# analogmic.net
KiCad netlist of a schematic drawn in EAGLE
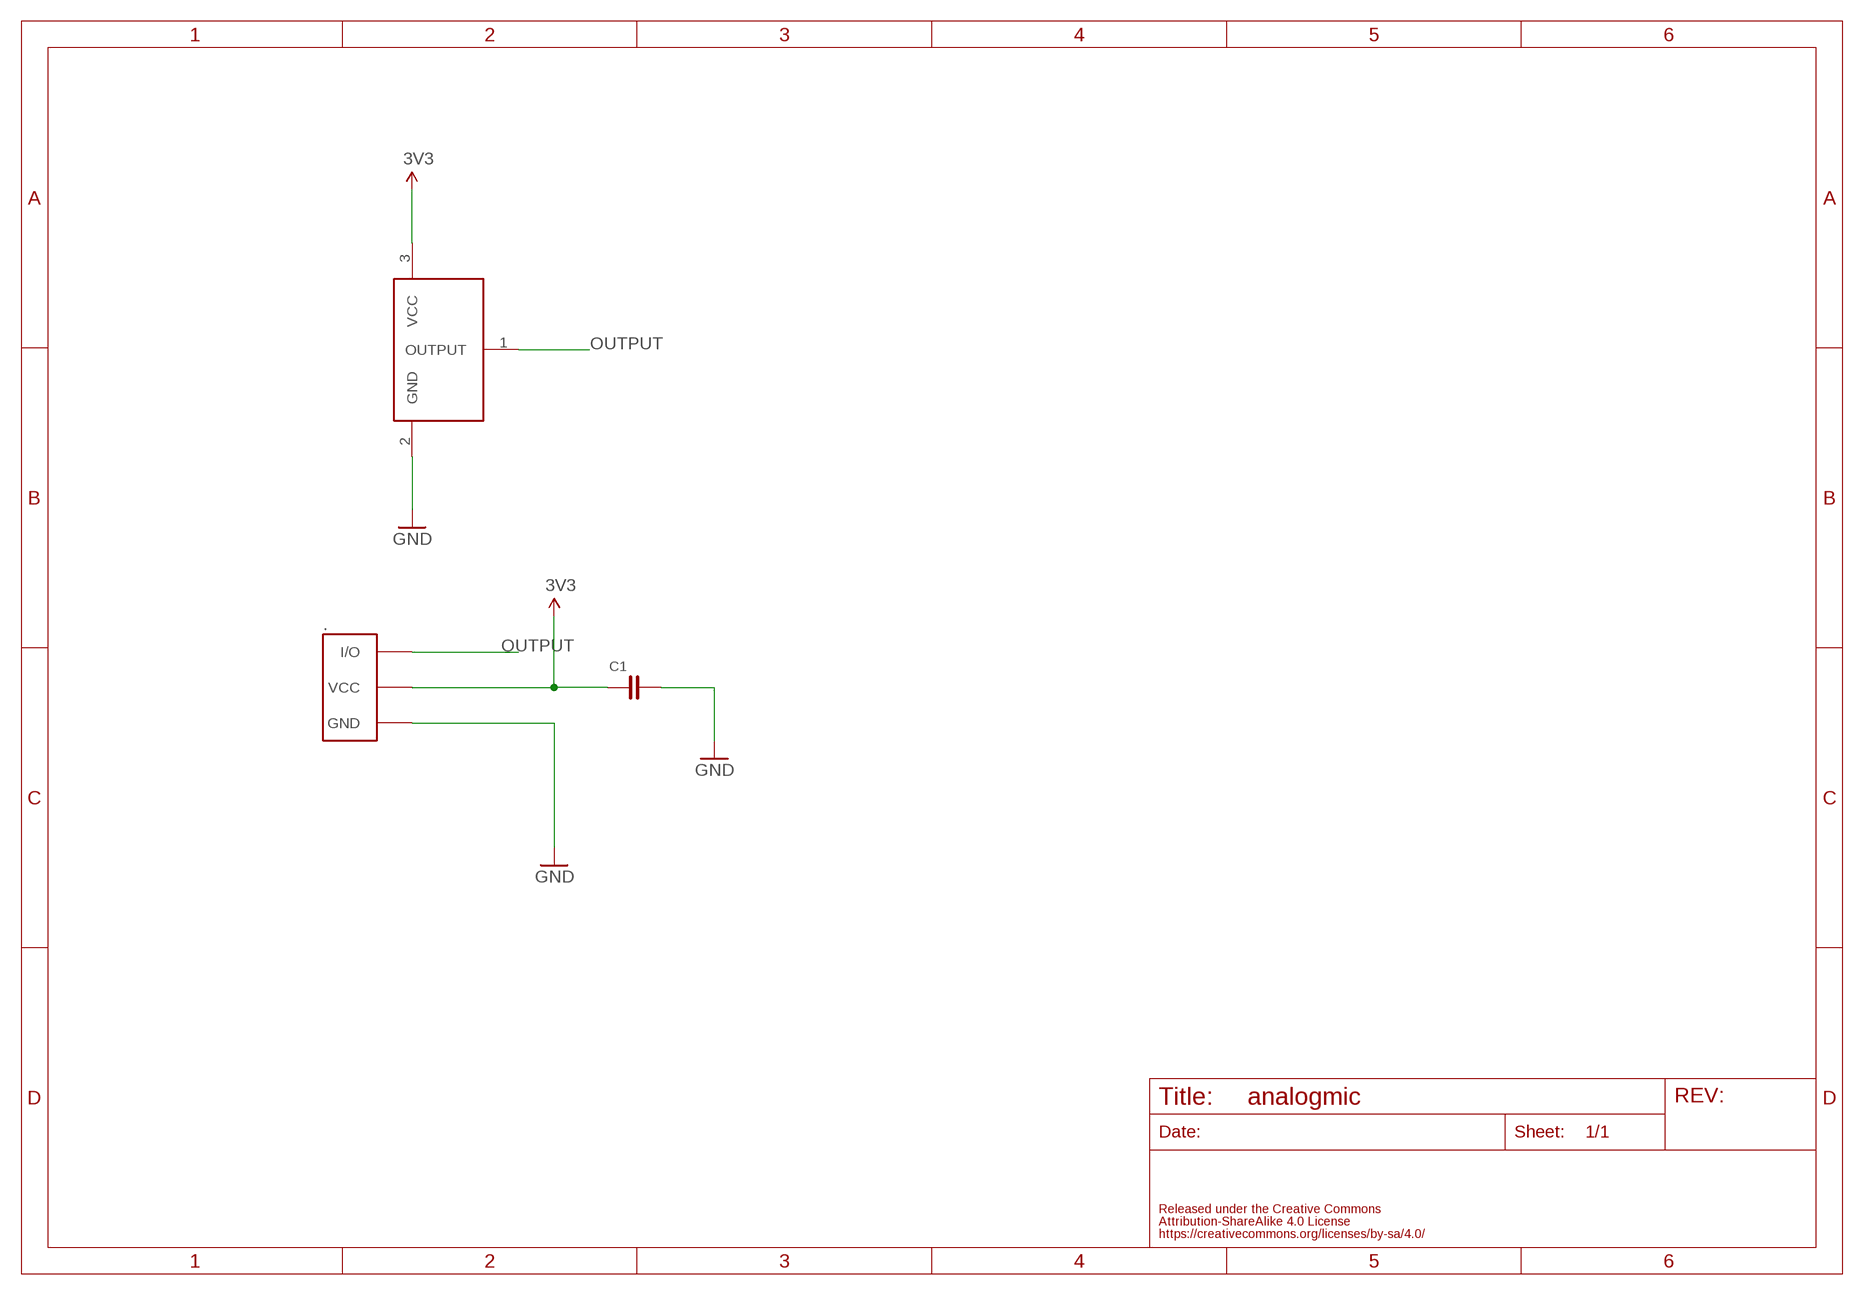
[diagram p0: schematic, sheet 1]

(export (version "E")
  (design (tool "Eeschema 10.0.6"))
  (components
    (comp (ref ".")
      (value "FABO_BRICK_3PIN-S03B-PASK-2")
      (footprint "eagle-import:FABO_BRICK_3PIN_S03B-PASK-2")
      (libsource (lib "eagle-import") (part "FABO_BRICK_3PIN-S03B-PASK-2"))
    )
    (comp (ref "C1")
      (value "CAPACITOR-0603")
      (footprint "eagle-import:0603")
      (libsource (lib "eagle-import") (part "CAPACITOR-0603"))
    )
    (comp (ref "ICS-40310")
      (value "ANALOG-MIC")
      (footprint "eagle-import:ICS40310")
      (libsource (lib "eagle-import") (part "ANALOG-MIC"))
    )
  )
  (nets
    (net (code "1") (name "/OUTPUT") (class "Default")
      (node (ref ".") (pin "I/O") (pinfunction "I/O_I/O") (pintype "bidirectional"))
      (node (ref "ICS-40310") (pin "1") (pinfunction "OUTPUT_1") (pintype "bidirectional"))
    )
    (net (code "2") (name "3V3") (class "Default")
      (node (ref ".") (pin "VCC") (pinfunction "VCC_VCC") (pintype "bidirectional"))
      (node (ref "C1") (pin "1") (pinfunction "1_1") (pintype "passive"))
      (node (ref "ICS-40310") (pin "3") (pinfunction "VCC_3") (pintype "bidirectional"))
    )
    (net (code "3") (name "GND") (class "Default")
      (node (ref ".") (pin "GND") (pinfunction "GND_GND") (pintype "bidirectional"))
      (node (ref "C1") (pin "2") (pinfunction "2_2") (pintype "passive"))
      (node (ref "ICS-40310") (pin "2") (pinfunction "GND_2") (pintype "bidirectional"))
    )
  )
)
